# Sheet1.net
KiCad netlist of a schematic drawn in Altium Designer
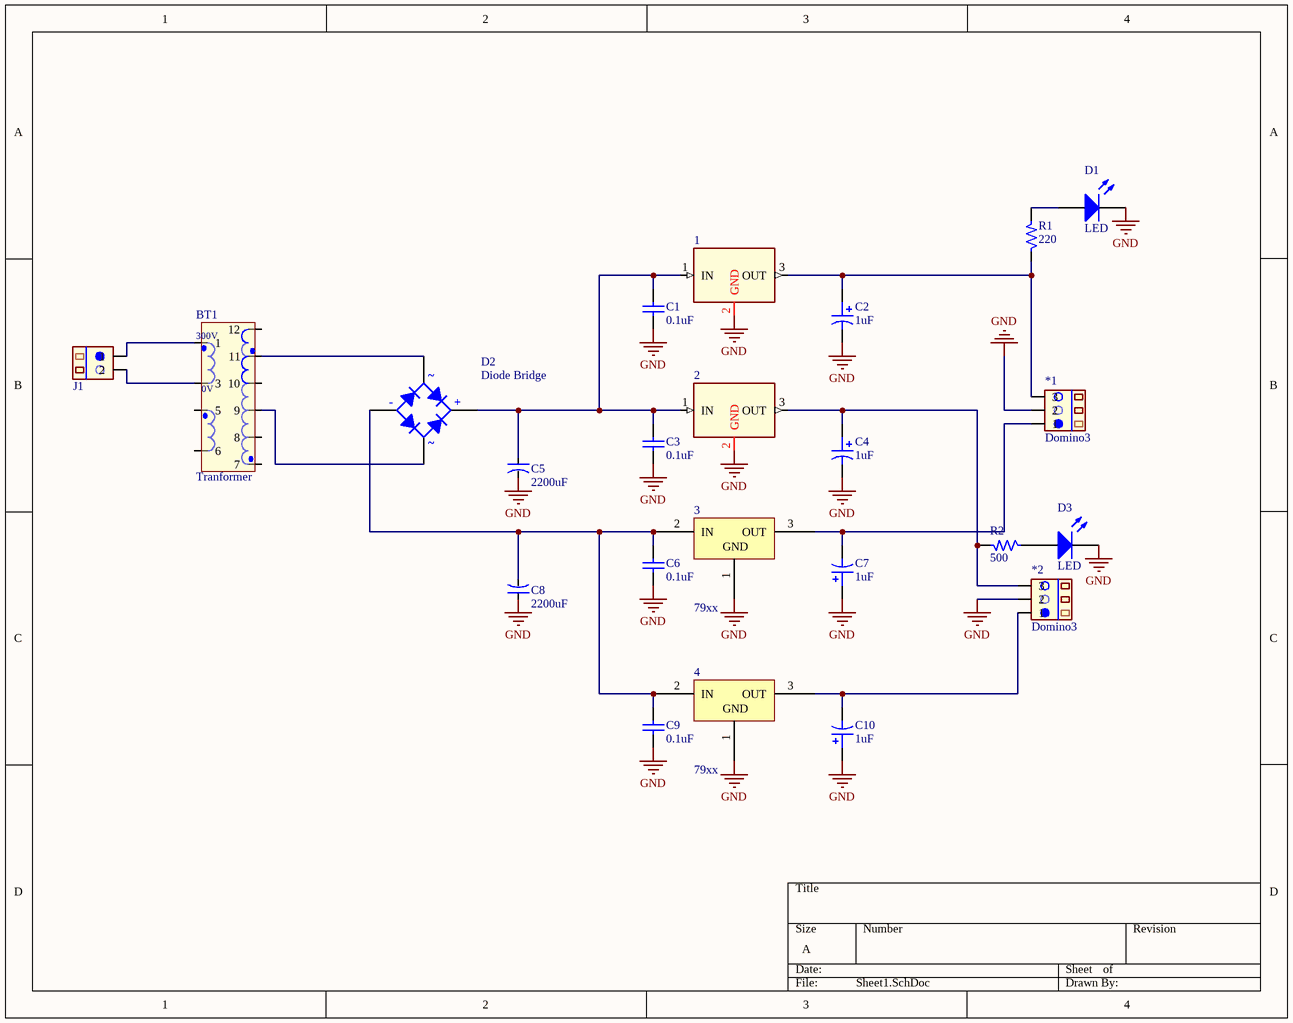
[diagram p0: Sheet1.SchDoc]

(export (version "E")
  (design (tool "Eeschema 10.0.6"))
  (components
    (comp (ref "*1") (value "Domino3") (footprint "Domino 3N") (libsource (lib "hphonglib") (part "Domino3")))
    (comp (ref "*2") (value "Domino3") (footprint "Domino 3N") (libsource (lib "hphonglib") (part "Domino3")))
    (comp (ref "1")
      (value "LM78xx")
      (footprint "TO-220")
      (description "Regulator")
      (fields
        (field (name "MANUFACTURER") "Fairchild Semiconductor Corporation")
        (field (name "TOLERANCE") "4 %")
        (field (name "PUBLISHER") "Hoang Nguyen")
      )
      (libsource (lib "hphonglib") (part "LM78xx"))
    )
    (comp (ref "2")
      (value "LM78xx")
      (footprint "TO-220")
      (description "Regulator")
      (fields
        (field (name "MANUFACTURER") "Fairchild Semiconductor Corporation")
        (field (name "TOLERANCE") "4 %")
        (field (name "PUBLISHER") "Hoang Nguyen")
      )
      (libsource (lib "hphonglib") (part "LM78xx"))
    )
    (comp (ref "3")
      (value "79xx")
      (footprint "TO-220-3")
      (description "3-Terminal 1A Negative Voltage Regulator")
      (libsource (lib "hphonglib") (part "79xx"))
    )
    (comp (ref "4")
      (value "79xx")
      (footprint "TO-220-3")
      (description "3-Terminal 1A Negative Voltage Regulator")
      (libsource (lib "hphonglib") (part "79xx"))
    )
    (comp (ref "BT1")
      (value "Tranformer")
      (footprint "BAX_EE32")
      (libsource (lib "hphonglib") (part "BAX_EE32"))
    )
    (comp (ref "C1")
      (value "0.1uF")
      (footprint "Cap Non-Pol 3mm")
      (description "Non-polarized Capacitor")
      (fields (field (name "Comment") "Cap Non-pol") (field (name "PUBLISHER") "Altium Limited"))
      (libsource (lib "hphonglib") (part "Cap Non-pol"))
    )
    (comp (ref "C2")
      (value "1uF")
      (footprint "RADIAL C")
      (description "Polarized Capacitor")
      (fields (field (name "Comment") "Cap Pol") (field (name "PUBLISHER") "Altium Limited"))
      (libsource (lib "hphonglib") (part "Cap Pol"))
    )
    (comp (ref "C3")
      (value "0.1uF")
      (footprint "Cap Non-Pol 3mm")
      (description "Non-polarized Capacitor")
      (fields (field (name "Comment") "Cap Non-pol") (field (name "PUBLISHER") "Altium Limited"))
      (libsource (lib "hphonglib") (part "Cap Non-pol"))
    )
    (comp (ref "C4")
      (value "1uF")
      (footprint "RADIAL C")
      (description "Polarized Capacitor")
      (fields (field (name "Comment") "Cap Pol") (field (name "PUBLISHER") "Altium Limited"))
      (libsource (lib "hphonglib") (part "Cap Pol"))
    )
    (comp (ref "C5")
      (value "2200uF")
      (footprint "RADIAL H(2200u_50V)")
      (description "Capacitor (Semiconductor SIM Model)")
      (fields (field (name "PUBLISHER") "Altium Limited"))
      (libsource (lib "LIBRARY") (part "CN-ALU-DIP"))
    )
    (comp (ref "C6")
      (value "0.1uF")
      (footprint "Cap Non-Pol 3mm")
      (description "Non-polarized Capacitor")
      (fields (field (name "Comment") "Cap Non-pol") (field (name "PUBLISHER") "Altium Limited"))
      (libsource (lib "hphonglib") (part "Cap Non-pol"))
    )
    (comp (ref "C7")
      (value "1uF")
      (footprint "RADIAL C")
      (description "Polarized Capacitor")
      (fields (field (name "Comment") "Cap Pol") (field (name "PUBLISHER") "Altium Limited"))
      (libsource (lib "hphonglib") (part "Cap Pol"))
    )
    (comp (ref "C8")
      (value "2200uF")
      (footprint "RADIAL H(2200u_50V)")
      (description "Capacitor (Semiconductor SIM Model)")
      (fields (field (name "PUBLISHER") "Altium Limited"))
      (libsource (lib "LIBRARY") (part "CN-ALU-DIP"))
    )
    (comp (ref "C9")
      (value "0.1uF")
      (footprint "Cap Non-Pol 3mm")
      (description "Non-polarized Capacitor")
      (fields (field (name "Comment") "Cap Non-pol") (field (name "PUBLISHER") "Altium Limited"))
      (libsource (lib "hphonglib") (part "Cap Non-pol"))
    )
    (comp (ref "C10")
      (value "1uF")
      (footprint "RADIAL C")
      (description "Polarized Capacitor")
      (fields (field (name "Comment") "Cap Pol") (field (name "PUBLISHER") "Altium Limited"))
      (libsource (lib "hphonglib") (part "Cap Pol"))
    )
    (comp (ref "D1")
      (value "LED")
      (footprint "LED-0 5mm BLUE")
      (description "Typical LED")
      (fields (field (name "PUBLISHER") "Altium Limited"))
      (libsource (lib "hphonglib") (part "LED"))
    )
    (comp (ref "D2")
      (value "Diode Bridge")
      (footprint "DIODE BRIDGE (1A)")
      (description "Full Wave Diode Bridge")
      (fields (field (name "PUBLISHER") "Altium Limited"))
      (libsource (lib "hphonglib") (part "Diode Bridge"))
    )
    (comp (ref "D3")
      (value "LED")
      (footprint "LED-0 5mm RED")
      (description "Typical LED")
      (fields (field (name "PUBLISHER") "Altium Limited"))
      (libsource (lib "hphonglib") (part "LED"))
    )
    (comp (ref "J1")
      (value "CON.Domino2")
      (footprint "Domino 2M")
      (description "2 pins Domino Header")
      (fields (field (name "PUBLISHER") "Hoang Nguyen"))
      (libsource (lib "hphonglib") (part "CON.Domino2"))
    )
    (comp (ref "R1")
      (value "220")
      (footprint "R1/4W")
      (description "Resistor 1/4W")
      (libsource (lib "hphonglib") (part "R"))
    )
    (comp (ref "R2")
      (value "500")
      (footprint "R1/4W")
      (description "Resistor 1/4W")
      (libsource (lib "hphonglib") (part "R"))
    )
  )
  (nets
    (net (code "1") (name "GND") (class "Default")
      (node (ref "*1") (pin "2") (pinfunction "2_2") (pintype "passive"))
      (node (ref "*2") (pin "2") (pinfunction "2_2") (pintype "passive"))
      (node (ref "1") (pin "2") (pinfunction "GND_2") (pintype "power_in"))
      (node (ref "2") (pin "2") (pinfunction "GND_2") (pintype "power_in"))
      (node (ref "3") (pin "1") (pinfunction "GND_1") (pintype "passive"))
      (node (ref "4") (pin "1") (pinfunction "GND_1") (pintype "passive"))
      (node (ref "C1") (pin "1") (pinfunction "1_1") (pintype "passive"))
      (node (ref "C10") (pin "1") (pinfunction "1_1") (pintype "passive"))
      (node (ref "C2") (pin "2") (pinfunction "2_2") (pintype "passive"))
      (node (ref "C3") (pin "1") (pinfunction "1_1") (pintype "passive"))
      (node (ref "C4") (pin "2") (pinfunction "2_2") (pintype "passive"))
      (node (ref "C5") (pin "2") (pinfunction "2_2") (pintype "passive"))
      (node (ref "C6") (pin "1") (pinfunction "1_1") (pintype "passive"))
      (node (ref "C7") (pin "1") (pinfunction "1_1") (pintype "passive"))
      (node (ref "C8") (pin "1") (pinfunction "1_1") (pintype "passive"))
      (node (ref "C9") (pin "1") (pinfunction "1_1") (pintype "passive"))
      (node (ref "D1") (pin "2") (pinfunction "K_2") (pintype "passive"))
      (node (ref "D3") (pin "2") (pinfunction "K_2") (pintype "passive"))
    )
    (net (code "2") (name "Net-(1-IN)") (class "Default")
      (node (ref "1") (pin "1") (pinfunction "IN_1") (pintype "input"))
      (node (ref "2") (pin "1") (pinfunction "IN_1") (pintype "input"))
      (node (ref "C1") (pin "2") (pinfunction "2_2") (pintype "passive"))
      (node (ref "C3") (pin "2") (pinfunction "2_2") (pintype "passive"))
      (node (ref "C5") (pin "1") (pinfunction "1_1") (pintype "passive"))
      (node (ref "D2") (pin "1") (pinfunction "K_1") (pintype "passive"))
    )
    (net (code "3") (name "Net-(1-OUT)") (class "Default")
      (node (ref "*1") (pin "3") (pinfunction "3_3") (pintype "passive"))
      (node (ref "1") (pin "3") (pinfunction "OUT_3") (pintype "output"))
      (node (ref "C2") (pin "1") (pinfunction "1_1") (pintype "passive"))
      (node (ref "R1") (pin "1") (pinfunction "1_1") (pintype "passive"))
    )
    (net (code "4") (name "Net-(2-OUT)") (class "Default")
      (node (ref "*2") (pin "3") (pinfunction "3_3") (pintype "passive"))
      (node (ref "2") (pin "3") (pinfunction "OUT_3") (pintype "output"))
      (node (ref "C4") (pin "1") (pinfunction "1_1") (pintype "passive"))
      (node (ref "R2") (pin "2") (pinfunction "2_2") (pintype "passive"))
    )
    (net (code "5") (name "Net-(3-IN)") (class "Default")
      (node (ref "3") (pin "2") (pinfunction "IN_2") (pintype "passive"))
      (node (ref "4") (pin "2") (pinfunction "IN_2") (pintype "passive"))
      (node (ref "C6") (pin "2") (pinfunction "2_2") (pintype "passive"))
      (node (ref "C8") (pin "2") (pinfunction "2_2") (pintype "passive"))
      (node (ref "C9") (pin "2") (pinfunction "2_2") (pintype "passive"))
      (node (ref "D2") (pin "4") (pinfunction "A_4") (pintype "passive"))
    )
    (net (code "6") (name "Net-(3-OUT)") (class "Default")
      (node (ref "*1") (pin "1") (pinfunction "1_1") (pintype "passive"))
      (node (ref "3") (pin "3") (pinfunction "OUT_3") (pintype "passive"))
      (node (ref "C7") (pin "2") (pinfunction "2_2") (pintype "passive"))
    )
    (net (code "7") (name "Net-(4-OUT)") (class "Default")
      (node (ref "*2") (pin "1") (pinfunction "1_1") (pintype "passive"))
      (node (ref "4") (pin "3") (pinfunction "OUT_3") (pintype "passive"))
      (node (ref "C10") (pin "2") (pinfunction "2_2") (pintype "passive"))
    )
    (net (code "8") (name "Net-(BT1-Pad1)") (class "Default")
      (node (ref "BT1") (pin "1") (pinfunction "1_1") (pintype "passive"))
      (node (ref "J1") (pin "1") (pinfunction "1_1") (pintype "passive"))
    )
    (net (code "9") (name "Net-(BT1-Pad3)") (class "Default")
      (node (ref "BT1") (pin "3") (pinfunction "3_3") (pintype "passive"))
      (node (ref "J1") (pin "2") (pinfunction "2_2") (pintype "passive"))
    )
    (net (code "10") (name "Net-(BT1-Pad9)") (class "Default")
      (node (ref "BT1") (pin "9") (pinfunction "9_9") (pintype "passive"))
      (node (ref "D2") (pin "3") (pinfunction "C_3") (pintype "passive"))
    )
    (net (code "11") (name "Net-(BT1-Pad11)") (class "Default")
      (node (ref "BT1") (pin "11") (pinfunction "11_11") (pintype "passive"))
      (node (ref "D2") (pin "2") (pinfunction "C_2") (pintype "passive"))
    )
    (net (code "12") (name "Net-(D1-A)") (class "Default")
      (node (ref "D1") (pin "1") (pinfunction "A_1") (pintype "passive"))
      (node (ref "R1") (pin "2") (pinfunction "2_2") (pintype "passive"))
    )
    (net (code "13") (name "Net-(D3-A)") (class "Default")
      (node (ref "D3") (pin "1") (pinfunction "A_1") (pintype "passive"))
      (node (ref "R2") (pin "1") (pinfunction "1_1") (pintype "passive"))
    )
    (net (code "14") (name "unconnected-(BT1-Pad5)") (class "Default")
      (node (ref "BT1") (pin "5") (pinfunction "5_5") (pintype "passive"))
    )
    (net (code "15") (name "unconnected-(BT1-Pad6)") (class "Default")
      (node (ref "BT1") (pin "6") (pinfunction "6_6") (pintype "passive"))
    )
    (net (code "16") (name "unconnected-(BT1-Pad7)") (class "Default")
      (node (ref "BT1") (pin "7") (pinfunction "7_7") (pintype "passive"))
    )
    (net (code "17") (name "unconnected-(BT1-Pad8)") (class "Default")
      (node (ref "BT1") (pin "8") (pinfunction "8_8") (pintype "passive"))
    )
    (net (code "18") (name "unconnected-(BT1-Pad10)") (class "Default")
      (node (ref "BT1") (pin "10") (pinfunction "10_10") (pintype "passive"))
    )
    (net (code "19") (name "unconnected-(BT1-Pad12)") (class "Default")
      (node (ref "BT1") (pin "12") (pinfunction "12_12") (pintype "passive"))
    )
  )
)
